# AODC_v1.net
KiCad netlist of a schematic drawn in EAGLE
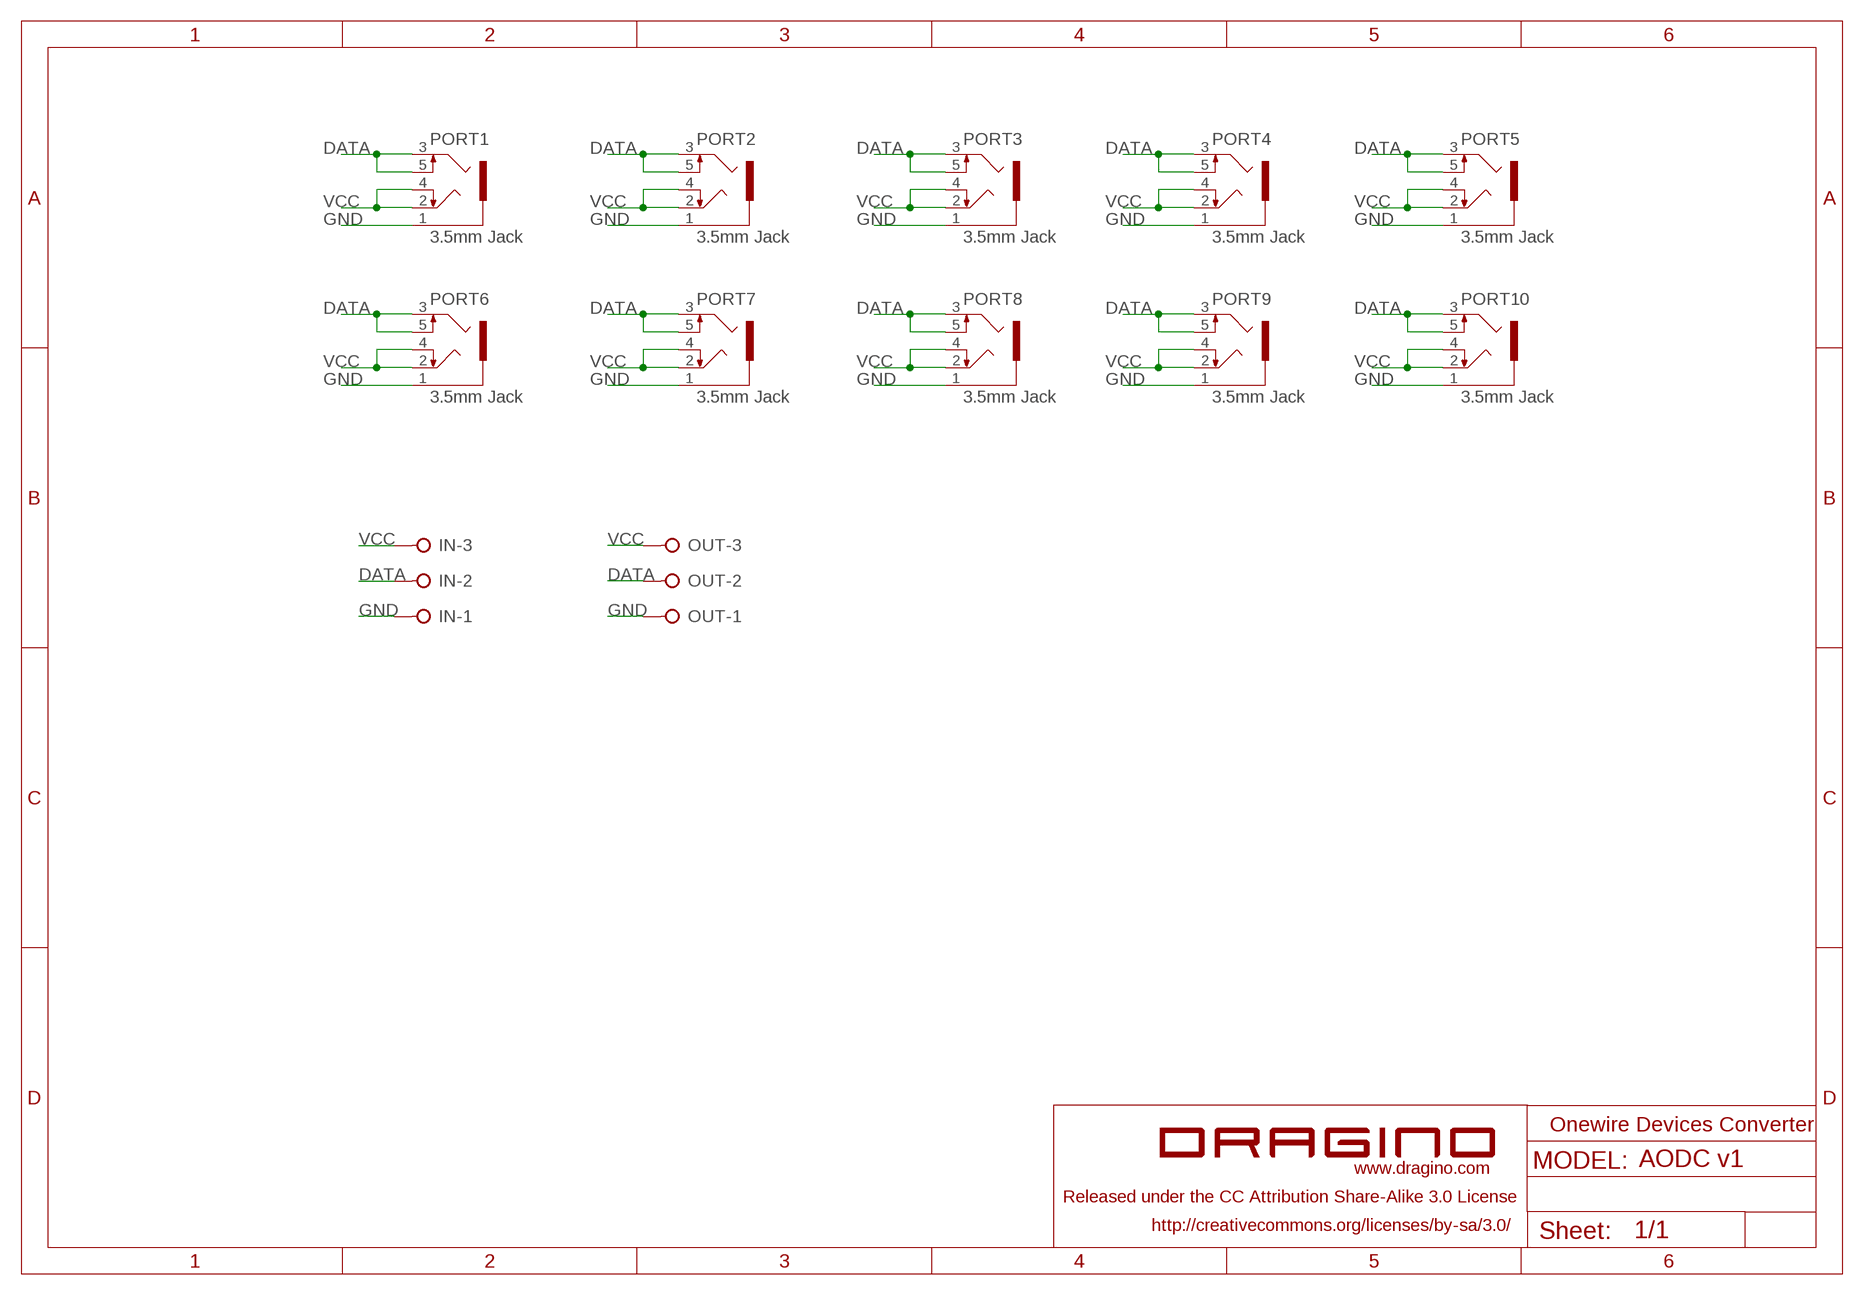
[diagram p0: schematic, sheet 1]

(export (version "E")
  (design (tool "Eeschema 10.0.6"))
  (components
    (comp (ref "IN")
      (value "SCREW-TERMINAL-3P")
      (footprint "eagle-import:W237-3E")
      (libsource (lib "eagle-import") (part "SCREW-TERMINAL-3P"))
    )
    (comp (ref "OUT")
      (value "SCREW-TERMINAL-3P")
      (footprint "eagle-import:W237-3E")
      (libsource (lib "eagle-import") (part "SCREW-TERMINAL-3P"))
    )
    (comp (ref "PORT1")
      (value "3.5mm Jack")
      (footprint "eagle-import:AUDIO-JACK-3.5MM")
      (libsource (lib "eagle-import") (part "AUDIO-JACK-3.5MMAUDIO-3.5MM"))
    )
    (comp (ref "PORT2")
      (value "3.5mm Jack")
      (footprint "eagle-import:AUDIO-JACK-3.5MM")
      (libsource (lib "eagle-import") (part "AUDIO-JACK-3.5MMAUDIO-3.5MM"))
    )
    (comp (ref "PORT3")
      (value "3.5mm Jack")
      (footprint "eagle-import:AUDIO-JACK-3.5MM")
      (libsource (lib "eagle-import") (part "AUDIO-JACK-3.5MMAUDIO-3.5MM"))
    )
    (comp (ref "PORT4")
      (value "3.5mm Jack")
      (footprint "eagle-import:AUDIO-JACK-3.5MM")
      (libsource (lib "eagle-import") (part "AUDIO-JACK-3.5MMAUDIO-3.5MM"))
    )
    (comp (ref "PORT5")
      (value "3.5mm Jack")
      (footprint "eagle-import:AUDIO-JACK-3.5MM")
      (libsource (lib "eagle-import") (part "AUDIO-JACK-3.5MMAUDIO-3.5MM"))
    )
    (comp (ref "PORT6")
      (value "3.5mm Jack")
      (footprint "eagle-import:AUDIO-JACK-3.5MM")
      (libsource (lib "eagle-import") (part "AUDIO-JACK-3.5MMAUDIO-3.5MM"))
    )
    (comp (ref "PORT7")
      (value "3.5mm Jack")
      (footprint "eagle-import:AUDIO-JACK-3.5MM")
      (libsource (lib "eagle-import") (part "AUDIO-JACK-3.5MMAUDIO-3.5MM"))
    )
    (comp (ref "PORT8")
      (value "3.5mm Jack")
      (footprint "eagle-import:AUDIO-JACK-3.5MM")
      (libsource (lib "eagle-import") (part "AUDIO-JACK-3.5MMAUDIO-3.5MM"))
    )
    (comp (ref "PORT9")
      (value "3.5mm Jack")
      (footprint "eagle-import:AUDIO-JACK-3.5MM")
      (libsource (lib "eagle-import") (part "AUDIO-JACK-3.5MMAUDIO-3.5MM"))
    )
    (comp (ref "PORT10")
      (value "3.5mm Jack")
      (footprint "eagle-import:AUDIO-JACK-3.5MM")
      (libsource (lib "eagle-import") (part "AUDIO-JACK-3.5MMAUDIO-3.5MM"))
    )
    (comp (ref "U$1")
      (value "LOGO-SILK")
      (footprint "eagle-import:LOGO-SILK-15MM")
      (libsource (lib "eagle-import") (part "LOGO-SILK"))
    )
  )
  (nets
    (net (code "1") (name "/DATA") (class "Default")
      (node (ref "IN") (pin "2") (pinfunction "KL_2") (pintype "passive"))
      (node (ref "OUT") (pin "2") (pinfunction "KL_2") (pintype "passive"))
      (node (ref "PORT1") (pin "3") (pinfunction "3_3") (pintype "passive"))
      (node (ref "PORT1") (pin "5") (pinfunction "5_5") (pintype "passive"))
      (node (ref "PORT10") (pin "3") (pinfunction "3_3") (pintype "passive"))
      (node (ref "PORT10") (pin "5") (pinfunction "5_5") (pintype "passive"))
      (node (ref "PORT2") (pin "3") (pinfunction "3_3") (pintype "passive"))
      (node (ref "PORT2") (pin "5") (pinfunction "5_5") (pintype "passive"))
      (node (ref "PORT3") (pin "3") (pinfunction "3_3") (pintype "passive"))
      (node (ref "PORT3") (pin "5") (pinfunction "5_5") (pintype "passive"))
      (node (ref "PORT4") (pin "3") (pinfunction "3_3") (pintype "passive"))
      (node (ref "PORT4") (pin "5") (pinfunction "5_5") (pintype "passive"))
      (node (ref "PORT5") (pin "3") (pinfunction "3_3") (pintype "passive"))
      (node (ref "PORT5") (pin "5") (pinfunction "5_5") (pintype "passive"))
      (node (ref "PORT6") (pin "3") (pinfunction "3_3") (pintype "passive"))
      (node (ref "PORT6") (pin "5") (pinfunction "5_5") (pintype "passive"))
      (node (ref "PORT7") (pin "3") (pinfunction "3_3") (pintype "passive"))
      (node (ref "PORT7") (pin "5") (pinfunction "5_5") (pintype "passive"))
      (node (ref "PORT8") (pin "3") (pinfunction "3_3") (pintype "passive"))
      (node (ref "PORT8") (pin "5") (pinfunction "5_5") (pintype "passive"))
      (node (ref "PORT9") (pin "3") (pinfunction "3_3") (pintype "passive"))
      (node (ref "PORT9") (pin "5") (pinfunction "5_5") (pintype "passive"))
    )
    (net (code "2") (name "/GND") (class "Default")
      (node (ref "IN") (pin "1") (pinfunction "KL_1") (pintype "passive"))
      (node (ref "OUT") (pin "1") (pinfunction "KL_1") (pintype "passive"))
      (node (ref "PORT1") (pin "1") (pinfunction "1_1") (pintype "passive"))
      (node (ref "PORT10") (pin "1") (pinfunction "1_1") (pintype "passive"))
      (node (ref "PORT2") (pin "1") (pinfunction "1_1") (pintype "passive"))
      (node (ref "PORT3") (pin "1") (pinfunction "1_1") (pintype "passive"))
      (node (ref "PORT4") (pin "1") (pinfunction "1_1") (pintype "passive"))
      (node (ref "PORT5") (pin "1") (pinfunction "1_1") (pintype "passive"))
      (node (ref "PORT6") (pin "1") (pinfunction "1_1") (pintype "passive"))
      (node (ref "PORT7") (pin "1") (pinfunction "1_1") (pintype "passive"))
      (node (ref "PORT8") (pin "1") (pinfunction "1_1") (pintype "passive"))
      (node (ref "PORT9") (pin "1") (pinfunction "1_1") (pintype "passive"))
    )
    (net (code "3") (name "/VCC") (class "Default")
      (node (ref "IN") (pin "3") (pinfunction "KL_3") (pintype "passive"))
      (node (ref "OUT") (pin "3") (pinfunction "KL_3") (pintype "passive"))
      (node (ref "PORT1") (pin "2") (pinfunction "2_2") (pintype "passive"))
      (node (ref "PORT1") (pin "4") (pinfunction "4_4") (pintype "passive"))
      (node (ref "PORT10") (pin "2") (pinfunction "2_2") (pintype "passive"))
      (node (ref "PORT10") (pin "4") (pinfunction "4_4") (pintype "passive"))
      (node (ref "PORT2") (pin "2") (pinfunction "2_2") (pintype "passive"))
      (node (ref "PORT2") (pin "4") (pinfunction "4_4") (pintype "passive"))
      (node (ref "PORT3") (pin "2") (pinfunction "2_2") (pintype "passive"))
      (node (ref "PORT3") (pin "4") (pinfunction "4_4") (pintype "passive"))
      (node (ref "PORT4") (pin "2") (pinfunction "2_2") (pintype "passive"))
      (node (ref "PORT4") (pin "4") (pinfunction "4_4") (pintype "passive"))
      (node (ref "PORT5") (pin "2") (pinfunction "2_2") (pintype "passive"))
      (node (ref "PORT5") (pin "4") (pinfunction "4_4") (pintype "passive"))
      (node (ref "PORT6") (pin "2") (pinfunction "2_2") (pintype "passive"))
      (node (ref "PORT6") (pin "4") (pinfunction "4_4") (pintype "passive"))
      (node (ref "PORT7") (pin "2") (pinfunction "2_2") (pintype "passive"))
      (node (ref "PORT7") (pin "4") (pinfunction "4_4") (pintype "passive"))
      (node (ref "PORT8") (pin "2") (pinfunction "2_2") (pintype "passive"))
      (node (ref "PORT8") (pin "4") (pinfunction "4_4") (pintype "passive"))
      (node (ref "PORT9") (pin "2") (pinfunction "2_2") (pintype "passive"))
      (node (ref "PORT9") (pin "4") (pinfunction "4_4") (pintype "passive"))
    )
  )
)
